# 02_Power.net
KiCad netlist of a schematic drawn in Altium Designer
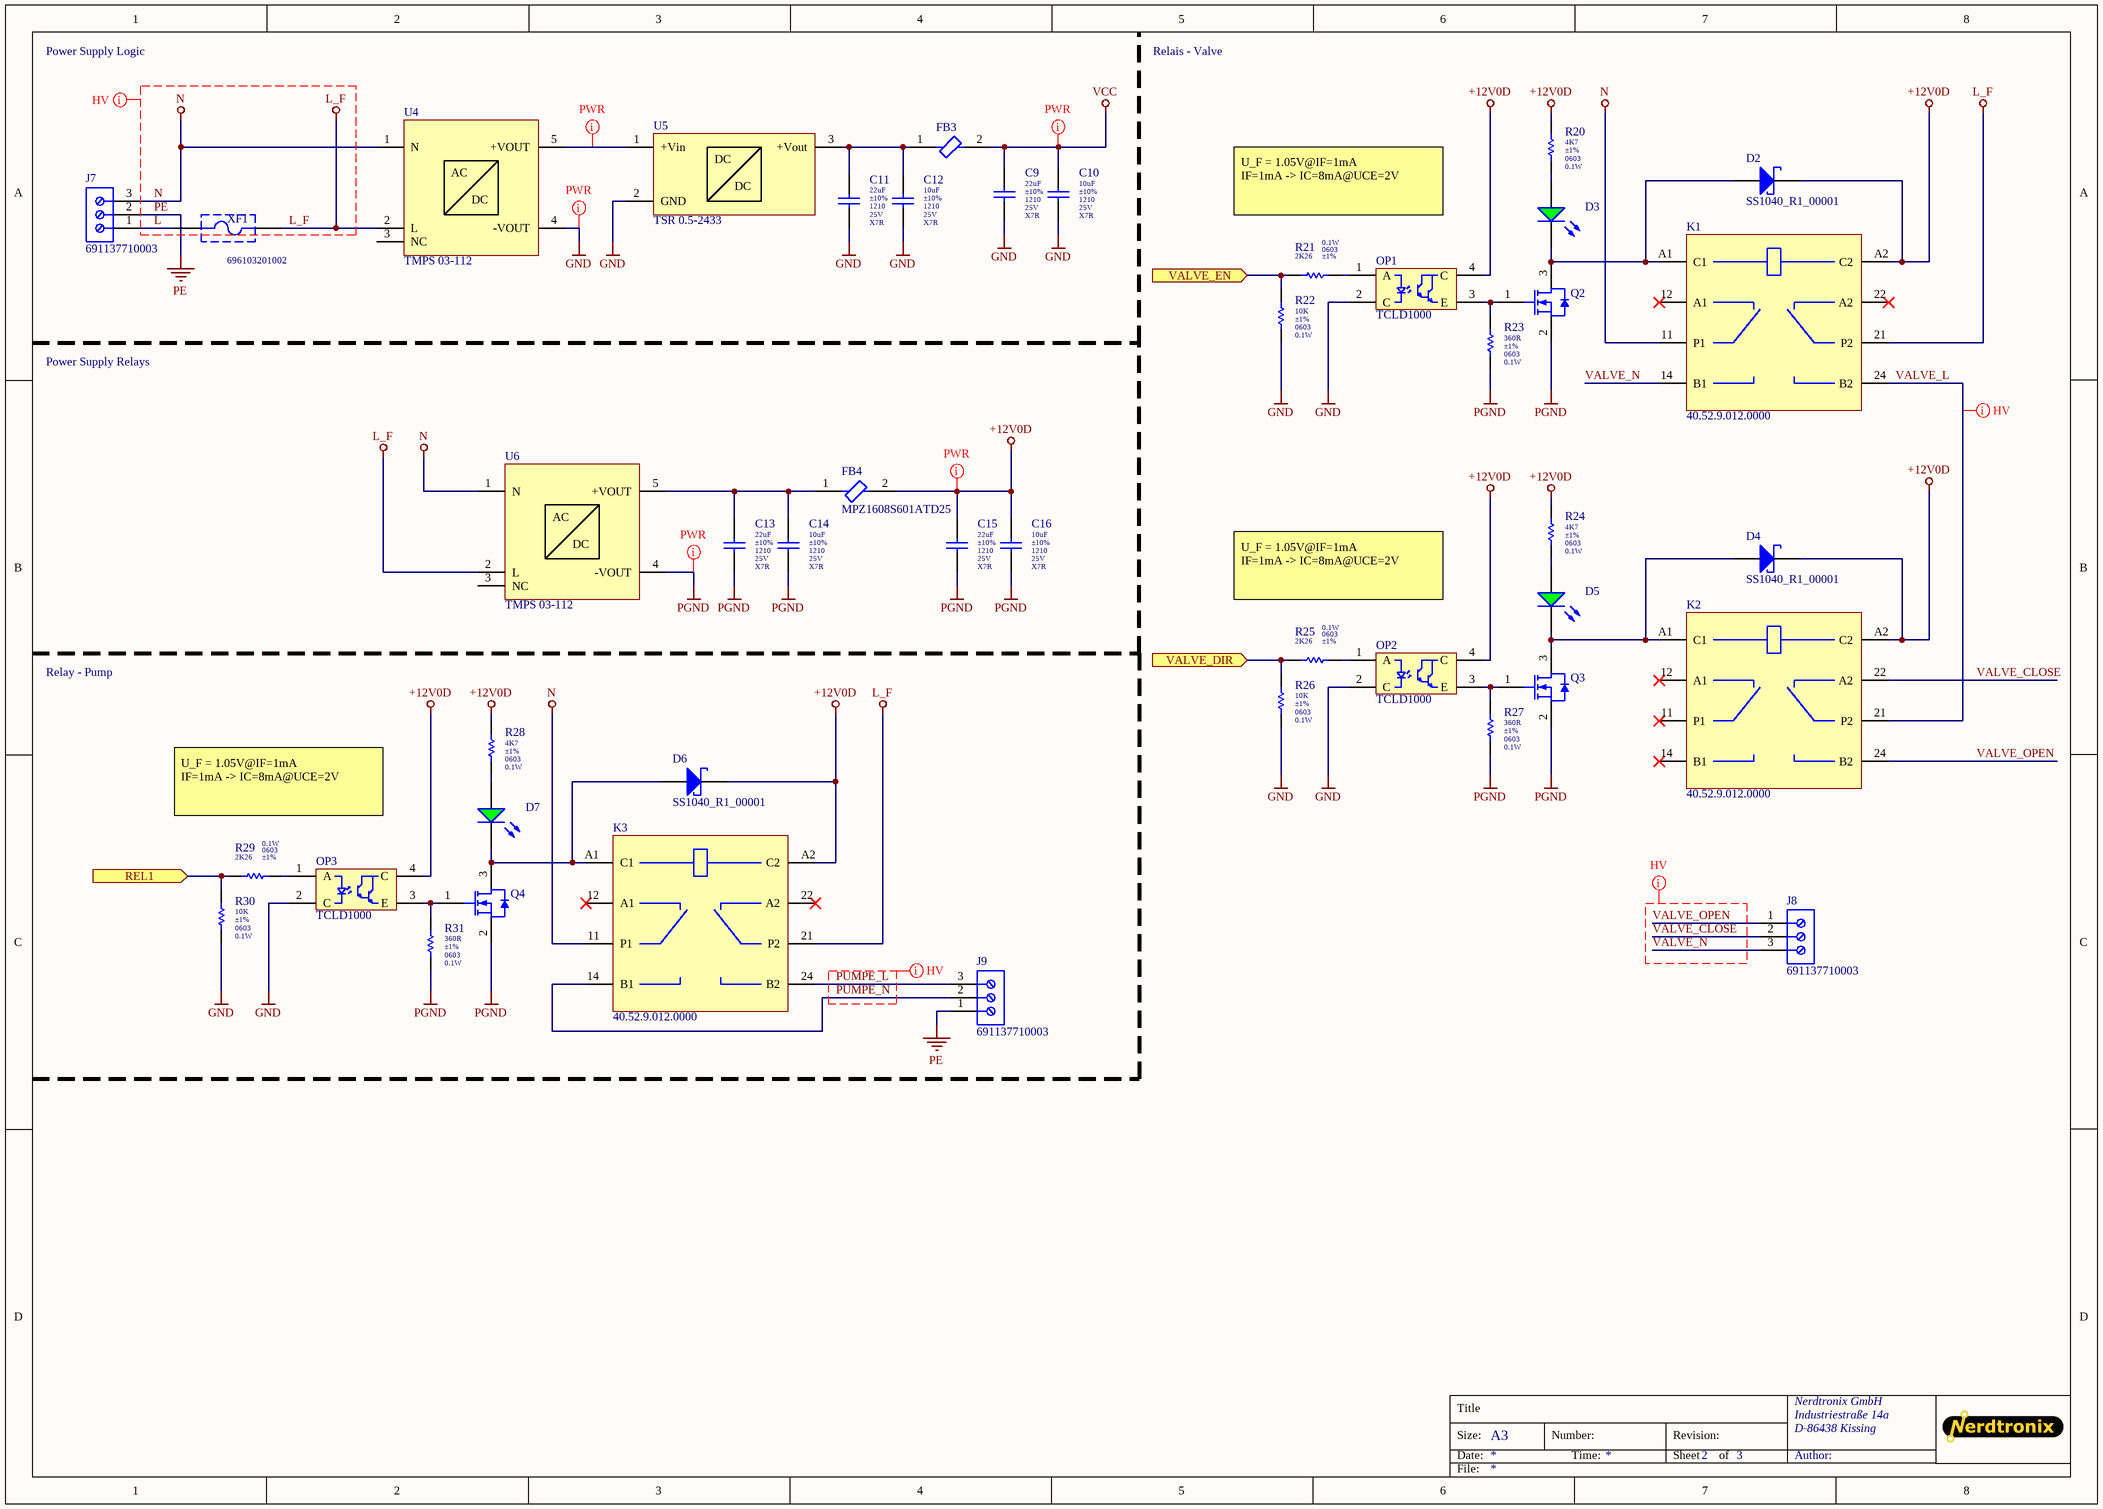
[diagram p0: 02_Power.SchDoc]

(export (version "E")
  (design (tool "Eeschema 10.0.6"))
  (components
    (comp (ref "C9")
      (value "22uF")
      (footprint "C_1210_B")
      (description "CAP 22uF 25V 1210 ±10% X7R")
      (fields
        (field (name "TOLERANCE") "±10%")
        (field (name "PACKAGE") "1210")
        (field (name "VOLTAGE") "25V")
        (field (name "DIELECTRIC") "X7R")
        (field (name "MANUFACTURER") "Samsung")
        (field (name "MANUFACTURER PART NUMBER") "CL32B226KAJNNNE")
        (field (name "CREATOR") "MSt 31-08-21")
      )
      (libsource (lib "Nerdtronix GmbH") (part "CAP"))
    )
    (comp (ref "C10")
      (value "10uF")
      (footprint "C_1210_B")
      (description "CAP 10uF 25V 1210 ±10% X7R")
      (fields
        (field (name "TOLERANCE") "±10%")
        (field (name "PACKAGE") "1210")
        (field (name "VOLTAGE") "25V")
        (field (name "DIELECTRIC") "X7R")
        (field (name "MANUFACTURER PART NUMBER") "CL32B106KAJNNNE")
        (field (name "MANUFACTURER") "Samsung")
        (field (name "CREATOR") "MSt 31-08-21")
      )
      (libsource (lib "Nerdtronix GmbH") (part "CAP"))
    )
    (comp (ref "C11")
      (value "22uF")
      (footprint "C_1210_B")
      (description "CAP 22uF 25V 1210 ±10% X7R")
      (fields
        (field (name "TOLERANCE") "±10%")
        (field (name "PACKAGE") "1210")
        (field (name "VOLTAGE") "25V")
        (field (name "DIELECTRIC") "X7R")
        (field (name "MANUFACTURER") "Samsung")
        (field (name "MANUFACTURER PART NUMBER") "CL32B226KAJNNNE")
        (field (name "CREATOR") "MSt 31-08-21")
      )
      (libsource (lib "Nerdtronix GmbH") (part "CAP"))
    )
    (comp (ref "C12")
      (value "10uF")
      (footprint "C_1210_B")
      (description "CAP 10uF 25V 1210 ±10% X7R")
      (fields
        (field (name "TOLERANCE") "±10%")
        (field (name "PACKAGE") "1210")
        (field (name "VOLTAGE") "25V")
        (field (name "DIELECTRIC") "X7R")
        (field (name "MANUFACTURER PART NUMBER") "CL32B106KAJNNNE")
        (field (name "MANUFACTURER") "Samsung")
        (field (name "CREATOR") "MSt 31-08-21")
      )
      (libsource (lib "Nerdtronix GmbH") (part "CAP"))
    )
    (comp (ref "C13")
      (value "22uF")
      (footprint "C_1210_B")
      (description "CAP 22uF 25V 1210 ±10% X7R")
      (fields
        (field (name "TOLERANCE") "±10%")
        (field (name "PACKAGE") "1210")
        (field (name "VOLTAGE") "25V")
        (field (name "DIELECTRIC") "X7R")
        (field (name "MANUFACTURER") "Samsung")
        (field (name "MANUFACTURER PART NUMBER") "CL32B226KAJNNNE")
        (field (name "CREATOR") "MSt 31-08-21")
      )
      (libsource (lib "Nerdtronix GmbH") (part "CAP"))
    )
    (comp (ref "C14")
      (value "10uF")
      (footprint "C_1210_B")
      (description "CAP 10uF 25V 1210 ±10% X7R")
      (fields
        (field (name "TOLERANCE") "±10%")
        (field (name "PACKAGE") "1210")
        (field (name "VOLTAGE") "25V")
        (field (name "DIELECTRIC") "X7R")
        (field (name "MANUFACTURER PART NUMBER") "CL32B106KAJNNNE")
        (field (name "MANUFACTURER") "Samsung")
        (field (name "CREATOR") "MSt 31-08-21")
      )
      (libsource (lib "Nerdtronix GmbH") (part "CAP"))
    )
    (comp (ref "C15")
      (value "22uF")
      (footprint "C_1210_B")
      (description "CAP 22uF 25V 1210 ±10% X7R")
      (fields
        (field (name "TOLERANCE") "±10%")
        (field (name "PACKAGE") "1210")
        (field (name "VOLTAGE") "25V")
        (field (name "DIELECTRIC") "X7R")
        (field (name "MANUFACTURER") "Samsung")
        (field (name "MANUFACTURER PART NUMBER") "CL32B226KAJNNNE")
        (field (name "CREATOR") "MSt 31-08-21")
      )
      (libsource (lib "Nerdtronix GmbH") (part "CAP"))
    )
    (comp (ref "C16")
      (value "10uF")
      (footprint "C_1210_B")
      (description "CAP 10uF 25V 1210 ±10% X7R")
      (fields
        (field (name "TOLERANCE") "±10%")
        (field (name "PACKAGE") "1210")
        (field (name "VOLTAGE") "25V")
        (field (name "DIELECTRIC") "X7R")
        (field (name "MANUFACTURER PART NUMBER") "CL32B106KAJNNNE")
        (field (name "MANUFACTURER") "Samsung")
        (field (name "CREATOR") "MSt 31-08-21")
      )
      (libsource (lib "Nerdtronix GmbH") (part "CAP"))
    )
    (comp (ref "D2")
      (value "SS1040_R1_00001")
      (footprint "SS1040_R1_00001")
      (description "Schottky Diode, 0.55V UF@IF=1A, 1A IF_max, SOD-123")
      (fields (field (name "MANUFACTURER") "Panjit International") (field (name "CREATOR") "MSt 06-02-22"))
      (libsource (lib "Nerdtronix GmbH") (part "SS1040_R1_00001"))
    )
    (comp (ref "D3")
      (value "SML-D12P8WT86")
      (footprint "0603 LED")
      (description "Green LED 0603")
      (fields (field (name "MANUFACTURER") "Rohm Semiconductor") (field (name "CREATOR") "MSt 31-01-22"))
      (libsource (lib "Nerdtronix GmbH") (part "SML-D12P8W"))
    )
    (comp (ref "D4")
      (value "SS1040_R1_00001")
      (footprint "SS1040_R1_00001")
      (description "Schottky Diode, 0.55V UF@IF=1A, 1A IF_max, SOD-123")
      (fields (field (name "MANUFACTURER") "Panjit International") (field (name "CREATOR") "MSt 06-02-22"))
      (libsource (lib "Nerdtronix GmbH") (part "SS1040_R1_00001"))
    )
    (comp (ref "D5")
      (value "SML-D12P8WT86")
      (footprint "0603 LED")
      (description "Green LED 0603")
      (fields (field (name "MANUFACTURER") "Rohm Semiconductor") (field (name "CREATOR") "MSt 31-01-22"))
      (libsource (lib "Nerdtronix GmbH") (part "SML-D12P8W"))
    )
    (comp (ref "D6")
      (value "SS1040_R1_00001")
      (footprint "SS1040_R1_00001")
      (description "Schottky Diode, 0.55V UF@IF=1A, 1A IF_max, SOD-123")
      (fields (field (name "MANUFACTURER") "Panjit International") (field (name "CREATOR") "MSt 06-02-22"))
      (libsource (lib "Nerdtronix GmbH") (part "SS1040_R1_00001"))
    )
    (comp (ref "D7")
      (value "SML-D12P8WT86")
      (footprint "0603 LED")
      (description "Green LED 0603")
      (fields (field (name "MANUFACTURER") "Rohm Semiconductor") (field (name "CREATOR") "MSt 31-01-22"))
      (libsource (lib "Nerdtronix GmbH") (part "SML-D12P8W"))
    )
    (comp (ref "FB3")
      (value "MPZ1608S601ATD25")
      (footprint "MPZ1608S601ATD25")
      (description "SMD Ferrit Bead 600Ω@100MHz 1A DCR 150mΩ")
      (fields (field (name "MANUFACTURER") "TDK") (field (name "CREATOR") "MSt 03-08-23"))
      (libsource (lib "Nerdtronix GmbH") (part "BBUP00100505121Y00"))
    )
    (comp (ref "FB4")
      (value "MPZ1608S601ATD25")
      (footprint "MPZ1608S601ATD25")
      (description "SMD Ferrit Bead 600Ω@100MHz 1A DCR 150mΩ")
      (fields (field (name "MANUFACTURER") "TDK") (field (name "CREATOR") "MSt 03-08-23"))
      (libsource (lib "Nerdtronix GmbH") (part "BBUP00100505121Y00"))
    )
    (comp (ref "J7")
      (value "691137710003")
      (footprint "691137710003")
      (description "WR-TBL Serie 1377 Horizontal Entry, Pressure Clamp, THT, Pitch 5mm, 3p")
      (fields (field (name "MANUFACTURER") "Wuerth Elektronik") (field (name "CREATOR") "MSt 08-12-21"))
      (libsource (lib "Nerdtronix GmbH") (part "691137710003"))
    )
    (comp (ref "J8")
      (value "691137710003")
      (footprint "691137710003")
      (description "WR-TBL Serie 1377 Horizontal Entry, Pressure Clamp, THT, Pitch 5mm, 3p")
      (fields (field (name "MANUFACTURER") "Wuerth Elektronik") (field (name "CREATOR") "MSt 08-12-21"))
      (libsource (lib "Nerdtronix GmbH") (part "691137710003"))
    )
    (comp (ref "J9")
      (value "691137710003")
      (footprint "691137710003")
      (description "WR-TBL Serie 1377 Horizontal Entry, Pressure Clamp, THT, Pitch 5mm, 3p")
      (fields (field (name "MANUFACTURER") "Wuerth Elektronik") (field (name "CREATOR") "MSt 08-12-21"))
      (libsource (lib "Nerdtronix GmbH") (part "691137710003"))
    )
    (comp (ref "K1")
      (value "40.52.9.012.0000")
      (footprint "40.52.9.012.0000")
      (description "Relay Double Pole, 12V Coil Voltage, 8.0 A Continous Switched Current")
      (fields (field (name "MANUFACTURER") "Finder Relays") (field (name "CREATOR") "MSt 08-12-21"))
      (libsource (lib "Nerdtronix GmbH") (part "40.52.9.012.0000"))
    )
    (comp (ref "K2")
      (value "40.52.9.012.0000")
      (footprint "40.52.9.012.0000")
      (description "Relay Double Pole, 12V Coil Voltage, 8.0 A Continous Switched Current")
      (fields (field (name "MANUFACTURER") "Finder Relays") (field (name "CREATOR") "MSt 08-12-21"))
      (libsource (lib "Nerdtronix GmbH") (part "40.52.9.012.0000"))
    )
    (comp (ref "K3")
      (value "40.52.9.012.0000")
      (footprint "40.52.9.012.0000")
      (description "Relay Double Pole, 12V Coil Voltage, 8.0 A Continous Switched Current")
      (fields (field (name "MANUFACTURER") "Finder Relays") (field (name "CREATOR") "MSt 08-12-21"))
      (libsource (lib "Nerdtronix GmbH") (part "40.52.9.012.0000"))
    )
    (comp (ref "OP1")
      (value "TCLD1000")
      (footprint "TCLD1000")
      (description "Optocoupler, Photodarlington Output")
      (fields (field (name "MANUFACTURER") "Vishay") (field (name "CREATOR") "MSt 23-08-22"))
      (libsource (lib "Nerdtronix GmbH") (part "TCLD1000"))
    )
    (comp (ref "OP2")
      (value "TCLD1000")
      (footprint "TCLD1000")
      (description "Optocoupler, Photodarlington Output")
      (fields (field (name "MANUFACTURER") "Vishay") (field (name "CREATOR") "MSt 23-08-22"))
      (libsource (lib "Nerdtronix GmbH") (part "TCLD1000"))
    )
    (comp (ref "OP3")
      (value "TCLD1000")
      (footprint "TCLD1000")
      (description "Optocoupler, Photodarlington Output")
      (fields (field (name "MANUFACTURER") "Vishay") (field (name "CREATOR") "MSt 23-08-22"))
      (libsource (lib "Nerdtronix GmbH") (part "TCLD1000"))
    )
    (comp (ref "Q2")
      (value "IRLML6244TRPBF")
      (footprint "IRLML6244TRPBF")
      (description "N-MOSFET Vds 20V Uth 1.1V ID 5.1A RDSon 27mΩ")
      (fields (field (name "MANUFACTURER") "Infineon Technologies") (field (name "CREATOR") "MSt 10-10-22"))
      (libsource (lib "Nerdtronix GmbH") (part "SSM3K329R"))
    )
    (comp (ref "Q3")
      (value "IRLML6244TRPBF")
      (footprint "IRLML6244TRPBF")
      (description "N-MOSFET Vds 20V Uth 1.1V ID 5.1A RDSon 27mΩ")
      (fields (field (name "MANUFACTURER") "Infineon Technologies") (field (name "CREATOR") "MSt 10-10-22"))
      (libsource (lib "Nerdtronix GmbH") (part "SSM3K329R"))
    )
    (comp (ref "Q4")
      (value "IRLML6244TRPBF")
      (footprint "IRLML6244TRPBF")
      (description "N-MOSFET Vds 20V Uth 1.1V ID 5.1A RDSon 27mΩ")
      (fields (field (name "MANUFACTURER") "Infineon Technologies") (field (name "CREATOR") "MSt 10-10-22"))
      (libsource (lib "Nerdtronix GmbH") (part "SSM3K329R"))
    )
    (comp (ref "R20")
      (value "4K7")
      (footprint "R_0603_B")
      (description "RES 4K7 0603 1% 0.1W")
      (fields
        (field (name "PACKAGE") "0603")
        (field (name "POWER") "0.1W")
        (field (name "TOLERANCE") "±1%")
        (field (name "MANUFACTURER") "Yageo")
        (field (name "MANUFACTURER PART NUMBER") "RC0603FR-074K7L")
        (field (name "CREATOR") "MSt 12-11-21")
      )
      (libsource (lib "Nerdtronix GmbH") (part "RES"))
    )
    (comp (ref "R21")
      (value "2K26")
      (footprint "R_0603_B")
      (description "RES 2K26 0603 1% 0.1W")
      (fields
        (field (name "PACKAGE") "0603")
        (field (name "POWER") "0.1W")
        (field (name "TOLERANCE") "±1%")
        (field (name "MANUFACTURER PART NUMBER") "RC0603FR-072K26L")
        (field (name "MANUFACTURER") "Yageo")
        (field (name "CREATOR") "MSt 26-08-21")
      )
      (libsource (lib "Nerdtronix GmbH") (part "RES"))
    )
    (comp (ref "R22")
      (value "10K")
      (footprint "R_0603_B")
      (description "RES 10K 0603 1% 0.1W")
      (fields
        (field (name "PACKAGE") "0603")
        (field (name "POWER") "0.1W")
        (field (name "TOLERANCE") "±1%")
        (field (name "MANUFACTURER") "Yageo")
        (field (name "MANUFACTURER PART NUMBER") "RC0603FR-0710KL")
        (field (name "CREATOR") "MSt 26-08-21")
      )
      (libsource (lib "Nerdtronix GmbH") (part "RES"))
    )
    (comp (ref "R23")
      (value "360R")
      (footprint "R_0603_B")
      (description "RES 360R 0603 1% 0.1W")
      (fields
        (field (name "PACKAGE") "0603")
        (field (name "POWER") "0.1W")
        (field (name "TOLERANCE") "±1%")
        (field (name "MANUFACTURER") "Yageo")
        (field (name "MANUFACTURER PART NUMBER") "RC0603FR-07360RL")
        (field (name "CREATOR") "MSt 12-11-21")
      )
      (libsource (lib "Nerdtronix GmbH") (part "RES"))
    )
    (comp (ref "R24")
      (value "4K7")
      (footprint "R_0603_B")
      (description "RES 4K7 0603 1% 0.1W")
      (fields
        (field (name "PACKAGE") "0603")
        (field (name "POWER") "0.1W")
        (field (name "TOLERANCE") "±1%")
        (field (name "MANUFACTURER") "Yageo")
        (field (name "MANUFACTURER PART NUMBER") "RC0603FR-074K7L")
        (field (name "CREATOR") "MSt 12-11-21")
      )
      (libsource (lib "Nerdtronix GmbH") (part "RES"))
    )
    (comp (ref "R25")
      (value "2K26")
      (footprint "R_0603_B")
      (description "RES 2K26 0603 1% 0.1W")
      (fields
        (field (name "PACKAGE") "0603")
        (field (name "POWER") "0.1W")
        (field (name "TOLERANCE") "±1%")
        (field (name "MANUFACTURER PART NUMBER") "RC0603FR-072K26L")
        (field (name "MANUFACTURER") "Yageo")
        (field (name "CREATOR") "MSt 26-08-21")
      )
      (libsource (lib "Nerdtronix GmbH") (part "RES"))
    )
    (comp (ref "R26")
      (value "10K")
      (footprint "R_0603_B")
      (description "RES 10K 0603 1% 0.1W")
      (fields
        (field (name "PACKAGE") "0603")
        (field (name "POWER") "0.1W")
        (field (name "TOLERANCE") "±1%")
        (field (name "MANUFACTURER") "Yageo")
        (field (name "MANUFACTURER PART NUMBER") "RC0603FR-0710KL")
        (field (name "CREATOR") "MSt 26-08-21")
      )
      (libsource (lib "Nerdtronix GmbH") (part "RES"))
    )
    (comp (ref "R27")
      (value "360R")
      (footprint "R_0603_B")
      (description "RES 360R 0603 1% 0.1W")
      (fields
        (field (name "PACKAGE") "0603")
        (field (name "POWER") "0.1W")
        (field (name "TOLERANCE") "±1%")
        (field (name "MANUFACTURER") "Yageo")
        (field (name "MANUFACTURER PART NUMBER") "RC0603FR-07360RL")
        (field (name "CREATOR") "MSt 12-11-21")
      )
      (libsource (lib "Nerdtronix GmbH") (part "RES"))
    )
    (comp (ref "R28")
      (value "4K7")
      (footprint "R_0603_B")
      (description "RES 4K7 0603 1% 0.1W")
      (fields
        (field (name "PACKAGE") "0603")
        (field (name "POWER") "0.1W")
        (field (name "TOLERANCE") "±1%")
        (field (name "MANUFACTURER") "Yageo")
        (field (name "MANUFACTURER PART NUMBER") "RC0603FR-074K7L")
        (field (name "CREATOR") "MSt 12-11-21")
      )
      (libsource (lib "Nerdtronix GmbH") (part "RES"))
    )
    (comp (ref "R29")
      (value "2K26")
      (footprint "R_0603_B")
      (description "RES 2K26 0603 1% 0.1W")
      (fields
        (field (name "PACKAGE") "0603")
        (field (name "POWER") "0.1W")
        (field (name "TOLERANCE") "±1%")
        (field (name "MANUFACTURER PART NUMBER") "RC0603FR-072K26L")
        (field (name "MANUFACTURER") "Yageo")
        (field (name "CREATOR") "MSt 26-08-21")
      )
      (libsource (lib "Nerdtronix GmbH") (part "RES"))
    )
    (comp (ref "R30")
      (value "10K")
      (footprint "R_0603_B")
      (description "RES 10K 0603 1% 0.1W")
      (fields
        (field (name "PACKAGE") "0603")
        (field (name "POWER") "0.1W")
        (field (name "TOLERANCE") "±1%")
        (field (name "MANUFACTURER") "Yageo")
        (field (name "MANUFACTURER PART NUMBER") "RC0603FR-0710KL")
        (field (name "CREATOR") "MSt 26-08-21")
      )
      (libsource (lib "Nerdtronix GmbH") (part "RES"))
    )
    (comp (ref "R31")
      (value "360R")
      (footprint "R_0603_B")
      (description "RES 360R 0603 1% 0.1W")
      (fields
        (field (name "PACKAGE") "0603")
        (field (name "POWER") "0.1W")
        (field (name "TOLERANCE") "±1%")
        (field (name "MANUFACTURER") "Yageo")
        (field (name "MANUFACTURER PART NUMBER") "RC0603FR-07360RL")
        (field (name "CREATOR") "MSt 12-11-21")
      )
      (libsource (lib "Nerdtronix GmbH") (part "RES"))
    )
    (comp (ref "U4")
      (value "TMPS 03-112")
      (footprint "TMPS 03")
      (description "Traco 3W AC/DC converter 12V Output")
      (fields (field (name "MANUFACTURER") "Traco Power") (field (name "CREATOR") "MSt 05-10-21"))
      (libsource (lib "Nerdtronix GmbH") (part "TMPS 03-112"))
    )
    (comp (ref "U5")
      (value "TSR 0.5-2433")
      (footprint "TSR 0.5-2433-Footprint-1")
      (description "Traco 0.5A DC/DC Converter 3.3V Output")
      (fields (field (name "MANUFACTURER") "Traco") (field (name "CREATOR") "MSt 15-11-21"))
      (libsource (lib "Nerdtronix GmbH") (part "TSR 0.5-2433"))
    )
    (comp (ref "U6")
      (value "TMPS 03-112")
      (footprint "TMPS 03")
      (description "Traco 3W AC/DC converter 12V Output")
      (fields (field (name "MANUFACTURER") "Traco Power") (field (name "CREATOR") "MSt 05-10-21"))
      (libsource (lib "Nerdtronix GmbH") (part "TMPS 03-112"))
    )
    (comp (ref "XF1")
      (value "696103201002")
      (footprint "696103201002")
      (description "WR-FSH Fuseholder THR Blocks PCB Clip Cover")
      (fields (field (name "MANUFACTURER") "Wuerth Elektronik") (field (name "CREATOR") "MSt 08-12-21"))
      (libsource (lib "Nerdtronix GmbH") (part "696103201002"))
    )
  )
  (nets
    (net (code "1") (name "+12V0D") (class "Default")
      (node (ref "C15") (pin "2") (pinfunction "2_2") (pintype "passive"))
      (node (ref "C16") (pin "2") (pinfunction "2_2") (pintype "passive"))
      (node (ref "D2") (pin "K") (pinfunction "K_K") (pintype "passive"))
      (node (ref "D4") (pin "K") (pinfunction "K_K") (pintype "passive"))
      (node (ref "D6") (pin "K") (pinfunction "K_K") (pintype "passive"))
      (node (ref "FB4") (pin "2") (pinfunction "2_2") (pintype "passive"))
      (node (ref "K1") (pin "A2") (pinfunction "C2_A2") (pintype "power_in"))
      (node (ref "K2") (pin "A2") (pinfunction "C2_A2") (pintype "power_in"))
      (node (ref "K3") (pin "A2") (pinfunction "C2_A2") (pintype "power_in"))
      (node (ref "OP1") (pin "4") (pinfunction "C_4") (pintype "passive"))
      (node (ref "OP2") (pin "4") (pinfunction "C_4") (pintype "passive"))
      (node (ref "OP3") (pin "4") (pinfunction "C_4") (pintype "passive"))
      (node (ref "R20") (pin "2") (pinfunction "2_2") (pintype "passive"))
      (node (ref "R24") (pin "2") (pinfunction "2_2") (pintype "passive"))
      (node (ref "R28") (pin "2") (pinfunction "2_2") (pintype "passive"))
    )
    (net (code "2") (name "/L") (class "Default")
      (node (ref "J7") (pin "1") (pinfunction "1_1") (pintype "passive"))
      (node (ref "XF1") (pin "1") (pinfunction "1_1") (pintype "passive"))
    )
    (net (code "3") (name "/PUMPE_L") (class "Default")
      (node (ref "J9") (pin "3") (pinfunction "3_3") (pintype "passive"))
      (node (ref "K3") (pin "24") (pinfunction "B2_24") (pintype "power_in"))
    )
    (net (code "4") (name "/PUMPE_N") (class "Default")
      (node (ref "J9") (pin "2") (pinfunction "2_2") (pintype "passive"))
      (node (ref "K3") (pin "14") (pinfunction "B1_14") (pintype "power_in"))
    )
    (net (code "5") (name "/REL1") (class "Default")
      (node (ref "R29") (pin "2") (pinfunction "2_2") (pintype "passive"))
      (node (ref "R30") (pin "2") (pinfunction "2_2") (pintype "passive"))
    )
    (net (code "6") (name "/VALVE_CLOSE") (class "Default")
      (node (ref "J8") (pin "2") (pinfunction "2_2") (pintype "passive"))
      (node (ref "K2") (pin "22") (pinfunction "A2_22") (pintype "power_in"))
    )
    (net (code "7") (name "/VALVE_DIR") (class "Default")
      (node (ref "R25") (pin "2") (pinfunction "2_2") (pintype "passive"))
      (node (ref "R26") (pin "2") (pinfunction "2_2") (pintype "passive"))
    )
    (net (code "8") (name "/VALVE_EN") (class "Default")
      (node (ref "R21") (pin "2") (pinfunction "2_2") (pintype "passive"))
      (node (ref "R22") (pin "2") (pinfunction "2_2") (pintype "passive"))
    )
    (net (code "9") (name "/VALVE_L") (class "Default")
      (node (ref "K1") (pin "24") (pinfunction "B2_24") (pintype "power_in"))
      (node (ref "K2") (pin "21") (pinfunction "P2_21") (pintype "power_in"))
    )
    (net (code "10") (name "/VALVE_N") (class "Default")
      (node (ref "J8") (pin "3") (pinfunction "3_3") (pintype "passive"))
      (node (ref "K1") (pin "14") (pinfunction "B1_14") (pintype "power_in"))
    )
    (net (code "11") (name "/VALVE_OPEN") (class "Default")
      (node (ref "J8") (pin "1") (pinfunction "1_1") (pintype "passive"))
      (node (ref "K2") (pin "24") (pinfunction "B2_24") (pintype "power_in"))
    )
    (net (code "12") (name "GND") (class "Default")
      (node (ref "C10") (pin "1") (pinfunction "1_1") (pintype "passive"))
      (node (ref "C11") (pin "1") (pinfunction "1_1") (pintype "passive"))
      (node (ref "C12") (pin "1") (pinfunction "1_1") (pintype "passive"))
      (node (ref "C9") (pin "1") (pinfunction "1_1") (pintype "passive"))
      (node (ref "OP1") (pin "2") (pinfunction "C_2") (pintype "passive"))
      (node (ref "OP2") (pin "2") (pinfunction "C_2") (pintype "passive"))
      (node (ref "OP3") (pin "2") (pinfunction "C_2") (pintype "passive"))
      (node (ref "R22") (pin "1") (pinfunction "1_1") (pintype "passive"))
      (node (ref "R26") (pin "1") (pinfunction "1_1") (pintype "passive"))
      (node (ref "R30") (pin "1") (pinfunction "1_1") (pintype "passive"))
      (node (ref "U4") (pin "4") (pinfunction "-VOUT_4") (pintype "power_in"))
      (node (ref "U5") (pin "2") (pinfunction "GND_2") (pintype "power_in"))
    )
    (net (code "13") (name "L_F") (class "Default")
      (node (ref "K1") (pin "21") (pinfunction "P2_21") (pintype "power_in"))
      (node (ref "K3") (pin "21") (pinfunction "P2_21") (pintype "power_in"))
      (node (ref "U4") (pin "2") (pinfunction "L_2") (pintype "power_in"))
      (node (ref "U6") (pin "2") (pinfunction "L_2") (pintype "power_in"))
      (node (ref "XF1") (pin "2") (pinfunction "2_2") (pintype "passive"))
    )
    (net (code "14") (name "N") (class "Default")
      (node (ref "J7") (pin "3") (pinfunction "3_3") (pintype "passive"))
      (node (ref "K1") (pin "11") (pinfunction "P1_11") (pintype "power_in"))
      (node (ref "K3") (pin "11") (pinfunction "P1_11") (pintype "power_in"))
      (node (ref "U4") (pin "1") (pinfunction "N_1") (pintype "power_in"))
      (node (ref "U6") (pin "1") (pinfunction "N_1") (pintype "power_in"))
    )
    (net (code "15") (name "Net-(D3-PadA)") (class "Default")
      (node (ref "D3") (pin "A") (pinfunction "A_A") (pintype "passive"))
      (node (ref "R20") (pin "1") (pinfunction "1_1") (pintype "passive"))
    )
    (net (code "16") (name "Net-(D5-PadA)") (class "Default")
      (node (ref "D5") (pin "A") (pinfunction "A_A") (pintype "passive"))
      (node (ref "R24") (pin "1") (pinfunction "1_1") (pintype "passive"))
    )
    (net (code "17") (name "Net-(D7-PadA)") (class "Default")
      (node (ref "D7") (pin "A") (pinfunction "A_A") (pintype "passive"))
      (node (ref "R28") (pin "1") (pinfunction "1_1") (pintype "passive"))
    )
    (net (code "18") (name "Net-(K1-C1)") (class "Default")
      (node (ref "D2") (pin "A") (pinfunction "A_A") (pintype "passive"))
      (node (ref "D3") (pin "K") (pinfunction "K_K") (pintype "passive"))
      (node (ref "K1") (pin "A1") (pinfunction "C1_A1") (pintype "power_in"))
      (node (ref "Q2") (pin "3") (pinfunction "D_3") (pintype "passive"))
    )
    (net (code "19") (name "Net-(K2-C1)") (class "Default")
      (node (ref "D4") (pin "A") (pinfunction "A_A") (pintype "passive"))
      (node (ref "D5") (pin "K") (pinfunction "K_K") (pintype "passive"))
      (node (ref "K2") (pin "A1") (pinfunction "C1_A1") (pintype "power_in"))
      (node (ref "Q3") (pin "3") (pinfunction "D_3") (pintype "passive"))
    )
    (net (code "20") (name "Net-(K3-C1)") (class "Default")
      (node (ref "D6") (pin "A") (pinfunction "A_A") (pintype "passive"))
      (node (ref "D7") (pin "K") (pinfunction "K_K") (pintype "passive"))
      (node (ref "K3") (pin "A1") (pinfunction "C1_A1") (pintype "power_in"))
      (node (ref "Q4") (pin "3") (pinfunction "D_3") (pintype "passive"))
    )
    (net (code "21") (name "Net-(OP1-A)") (class "Default")
      (node (ref "OP1") (pin "1") (pinfunction "A_1") (pintype "passive"))
      (node (ref "R21") (pin "1") (pinfunction "1_1") (pintype "passive"))
    )
    (net (code "22") (name "Net-(OP1-E)") (class "Default")
      (node (ref "OP1") (pin "3") (pinfunction "E_3") (pintype "passive"))
      (node (ref "Q2") (pin "1") (pinfunction "G_1") (pintype "passive"))
      (node (ref "R23") (pin "2") (pinfunction "2_2") (pintype "passive"))
    )
    (net (code "23") (name "Net-(OP2-A)") (class "Default")
      (node (ref "OP2") (pin "1") (pinfunction "A_1") (pintype "passive"))
      (node (ref "R25") (pin "1") (pinfunction "1_1") (pintype "passive"))
    )
    (net (code "24") (name "Net-(OP2-E)") (class "Default")
      (node (ref "OP2") (pin "3") (pinfunction "E_3") (pintype "passive"))
      (node (ref "Q3") (pin "1") (pinfunction "G_1") (pintype "passive"))
      (node (ref "R27") (pin "2") (pinfunction "2_2") (pintype "passive"))
    )
    (net (code "25") (name "Net-(OP3-A)") (class "Default")
      (node (ref "OP3") (pin "1") (pinfunction "A_1") (pintype "passive"))
      (node (ref "R29") (pin "1") (pinfunction "1_1") (pintype "passive"))
    )
    (net (code "26") (name "Net-(OP3-E)") (class "Default")
      (node (ref "OP3") (pin "3") (pinfunction "E_3") (pintype "passive"))
      (node (ref "Q4") (pin "1") (pinfunction "G_1") (pintype "passive"))
      (node (ref "R31") (pin "2") (pinfunction "2_2") (pintype "passive"))
    )
    (net (code "27") (name "Net-(U4-+VOUT)") (class "Default")
      (node (ref "U4") (pin "5") (pinfunction "+VOUT_5") (pintype "power_in"))
      (node (ref "U5") (pin "1") (pinfunction "+Vin_1") (pintype "power_in"))
    )
    (net (code "28") (name "Net-(U5-+Vout)") (class "Default")
      (node (ref "C11") (pin "2") (pinfunction "2_2") (pintype "passive"))
      (node (ref "C12") (pin "2") (pinfunction "2_2") (pintype "passive"))
      (node (ref "FB3") (pin "1") (pinfunction "1_1") (pintype "passive"))
      (node (ref "U5") (pin "3") (pinfunction "+Vout_3") (pintype "power_in"))
    )
    (net (code "29") (name "Net-(U6-+VOUT)") (class "Default")
      (node (ref "C13") (pin "2") (pinfunction "2_2") (pintype "passive"))
      (node (ref "C14") (pin "2") (pinfunction "2_2") (pintype "passive"))
      (node (ref "FB4") (pin "1") (pinfunction "1_1") (pintype "passive"))
      (node (ref "U6") (pin "5") (pinfunction "+VOUT_5") (pintype "power_in"))
    )
    (net (code "30") (name "PE") (class "Default")
      (node (ref "J7") (pin "2") (pinfunction "2_2") (pintype "passive"))
      (node (ref "J9") (pin "1") (pinfunction "1_1") (pintype "passive"))
    )
    (net (code "31") (name "PGND") (class "Default")
      (node (ref "C13") (pin "1") (pinfunction "1_1") (pintype "passive"))
      (node (ref "C14") (pin "1") (pinfunction "1_1") (pintype "passive"))
      (node (ref "C15") (pin "1") (pinfunction "1_1") (pintype "passive"))
      (node (ref "C16") (pin "1") (pinfunction "1_1") (pintype "passive"))
      (node (ref "Q2") (pin "2") (pinfunction "S_2") (pintype "passive"))
      (node (ref "Q3") (pin "2") (pinfunction "S_2") (pintype "passive"))
      (node (ref "Q4") (pin "2") (pinfunction "S_2") (pintype "passive"))
      (node (ref "R23") (pin "1") (pinfunction "1_1") (pintype "passive"))
      (node (ref "R27") (pin "1") (pinfunction "1_1") (pintype "passive"))
      (node (ref "R31") (pin "1") (pinfunction "1_1") (pintype "passive"))
      (node (ref "U6") (pin "4") (pinfunction "-VOUT_4") (pintype "power_in"))
    )
    (net (code "32") (name "VCC") (class "Default")
      (node (ref "C10") (pin "2") (pinfunction "2_2") (pintype "passive"))
      (node (ref "C9") (pin "2") (pinfunction "2_2") (pintype "passive"))
      (node (ref "FB3") (pin "2") (pinfunction "2_2") (pintype "passive"))
    )
    (net (code "33") (name "unconnected-(K1-A1-Pad12)") (class "Default")
      (node (ref "K1") (pin "12") (pinfunction "A1_12") (pintype "power_in+no_connect"))
    )
    (net (code "34") (name "unconnected-(K1-A2-Pad22)") (class "Default")
      (node (ref "K1") (pin "22") (pinfunction "A2_22") (pintype "power_in+no_connect"))
    )
    (net (code "35") (name "unconnected-(K2-A1-Pad12)") (class "Default")
      (node (ref "K2") (pin "12") (pinfunction "A1_12") (pintype "power_in+no_connect"))
    )
    (net (code "36") (name "unconnected-(K2-B1-Pad14)") (class "Default")
      (node (ref "K2") (pin "14") (pinfunction "B1_14") (pintype "power_in+no_connect"))
    )
    (net (code "37") (name "unconnected-(K2-P1-Pad11)") (class "Default")
      (node (ref "K2") (pin "11") (pinfunction "P1_11") (pintype "power_in+no_connect"))
    )
    (net (code "38") (name "unconnected-(K3-A1-Pad12)") (class "Default")
      (node (ref "K3") (pin "12") (pinfunction "A1_12") (pintype "power_in+no_connect"))
    )
    (net (code "39") (name "unconnected-(K3-A2-Pad22)") (class "Default")
      (node (ref "K3") (pin "22") (pinfunction "A2_22") (pintype "power_in+no_connect"))
    )
    (net (code "40") (name "unconnected-(U4-NC-Pad3)") (class "Default")
      (node (ref "U4") (pin "3") (pinfunction "NC_3") (pintype "passive"))
    )
    (net (code "41") (name "unconnected-(U6-NC-Pad3)") (class "Default")
      (node (ref "U6") (pin "3") (pinfunction "NC_3") (pintype "passive"))
    )
  )
)
